# RFR24_AMS_Design_-_Power_Supply_V1.net
KiCad netlist of a schematic drawn in Altium Designer
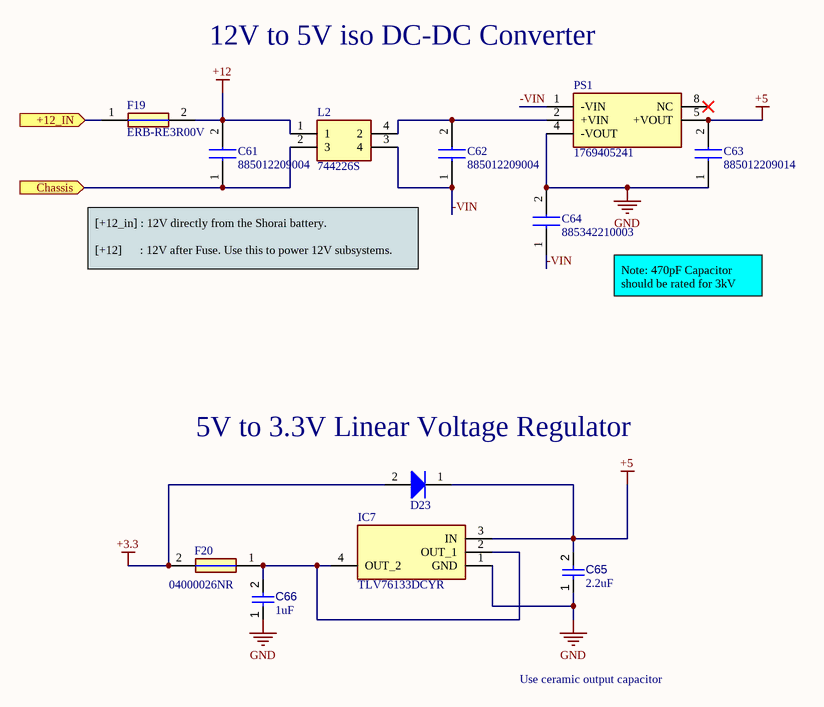
[diagram p0: RFR24 AMS Design - Power Supply V1.SchDoc]

(export (version "E")
  (design (tool "Eeschema 10.0.6"))
  (components
    (comp (ref "C61")
      (value "885012209004")
      (footprint "SamacSys:CAPC3225X220N")
      (description "Capacitor")
      (fields (field (name "MOUSER PART NUMBER") "710-885012209004"))
      (libsource (lib "*") (part "885012209004"))
    )
    (comp (ref "C62")
      (value "885012209004")
      (footprint "SamacSys:CAPC3225X220N")
      (description "Capacitor")
      (fields (field (name "MOUSER PART NUMBER") "710-885012209004"))
      (libsource (lib "*") (part "885012209004"))
    )
    (comp (ref "C63")
      (value "885012209014")
      (footprint "SamacSys:CAPC3225X220N")
      (description "Capacitor")
      (fields (field (name "MOUSER PART NUMBER") "710-885012209014"))
      (libsource (lib "*") (part "885012209014"))
    )
    (comp (ref "C64")
      (value "885342210003")
      (footprint "SamacSys:CAPC4620X220N")
      (description "Capacitor")
      (fields (field (name "MOUSER PART NUMBER") "710-885342210003"))
      (libsource (lib "*") (part "885342210003"))
    )
    (comp (ref "C65")
      (value "2.2uF")
      (footprint "CAPC2013X145X50LL20T25")
      (description "Chip Capacitor, 1 uF, +/-10%, 25 V, 0805 (2012 Metric)")
      (fields (field (name "TOLERANCE") "10%") (field (name "Comment") "Capacitor 1 uF +/- 10% 25 V 0805"))
      (libsource (lib "Rutgers University") (part "CAP-NP-2"))
    )
    (comp (ref "C66")
      (value "1uF")
      (footprint "CAPC2013X145X50LL20T25")
      (description "Chip Capacitor, 1 uF, +/-10%, 25 V, 0805 (2012 Metric)")
      (fields (field (name "TOLERANCE") "10%") (field (name "Comment") "Capacitor 1 uF +/- 10% 25 V 0805"))
      (libsource (lib "Rutgers University") (part "CAP-NP-2"))
    )
    (comp (ref "D23")
      (value "unknown")
      (footprint "INF-SOD323_V")
      (description "Silicon Schottky Diode, -55 to 125 degC, SOD323, Reel, Green")
      (fields (field (name "PARTNUMBER") "BAS170W") (field (name "MANUFACTURER") "Infineon"))
      (libsource (lib "Altium Content Vault") (part "INF-D_K1A2-2"))
    )
    (comp (ref "F19")
      (value "ERB-RE3R00V")
      (footprint "SamacSys:ERBRE0R50V")
      (description "Fuse")
      (fields (field (name "MOUSER PART NUMBER") "667-ERB-RE3R00V"))
      (libsource (lib "*") (part "ERB-RE3R00V"))
    )
    (comp (ref "F20")
      (value "04000026NR")
      (footprint "SamacSys:FUSC1508X58N")
      (description "Fuse")
      (fields (field (name "MOUSER PART NUMBER") "576-04000026NR"))
      (libsource (lib "*") (part "04000026NR"))
    )
    (comp (ref "IC7")
      (value "TLV76133DCYR")
      (footprint "SamacSys:SOT230P700X180-4N")
      (description "Integrated Circuit")
      (fields (field (name "MOUSER PART NUMBER") "595-TLV76133DCYR"))
      (libsource (lib "*") (part "TLV76133DCYR"))
    )
    (comp (ref "L2")
      (value "744226S")
      (footprint "SamacSys:WE-SL274")
      (description "Inductor")
      (fields (field (name "MOUSER PART NUMBER") "710-744226S"))
      (libsource (lib "*") (part "744226S"))
    )
    (comp (ref "PS1")
      (value "1769405241")
      (footprint "SamacSys:1769405241")
      (description "Power Supply")
      (libsource (lib "*") (part "1769405241"))
    )
  )
  (nets
    (net (code "1") (name "+3.3") (class "Default")
      (node (ref "D23") (pin "2") (pinfunction "A_2") (pintype "passive"))
      (node (ref "F20") (pin "2") (pinfunction "2_2") (pintype "passive"))
    )
    (net (code "2") (name "+5") (class "Default")
      (node (ref "C63") (pin "2") (pinfunction "2_2") (pintype "passive"))
      (node (ref "C65") (pin "2") (pinfunction "2_2") (pintype "passive"))
      (node (ref "D23") (pin "1") (pinfunction "K_1") (pintype "passive"))
      (node (ref "IC7") (pin "3") (pinfunction "IN_3") (pintype "passive"))
      (node (ref "PS1") (pin "5") (pinfunction "+VOUT_5") (pintype "passive"))
    )
    (net (code "3") (name "+12") (class "Default")
      (node (ref "C61") (pin "2") (pinfunction "2_2") (pintype "passive"))
      (node (ref "F19") (pin "2") (pinfunction "2_2") (pintype "passive"))
      (node (ref "L2") (pin "1") (pinfunction "1_1") (pintype "passive"))
    )
    (net (code "4") (name "/+12_IN") (class "Default")
      (node (ref "F19") (pin "1") (pinfunction "1_1") (pintype "passive"))
    )
    (net (code "5") (name "/-VIN") (class "Default")
      (node (ref "C62") (pin "1") (pinfunction "1_1") (pintype "passive"))
      (node (ref "C64") (pin "1") (pinfunction "1_1") (pintype "passive"))
      (node (ref "L2") (pin "3") (pinfunction "4_3") (pintype "passive"))
      (node (ref "PS1") (pin "1") (pinfunction "-VIN_1") (pintype "passive"))
    )
    (net (code "6") (name "/Chassis") (class "Default")
      (node (ref "C61") (pin "1") (pinfunction "1_1") (pintype "passive"))
      (node (ref "L2") (pin "2") (pinfunction "3_2") (pintype "passive"))
    )
    (net (code "7") (name "GND") (class "Default")
      (node (ref "C63") (pin "1") (pinfunction "1_1") (pintype "passive"))
      (node (ref "C64") (pin "2") (pinfunction "2_2") (pintype "passive"))
      (node (ref "C65") (pin "1") (pinfunction "1_1") (pintype "passive"))
      (node (ref "C66") (pin "1") (pinfunction "1_1") (pintype "passive"))
      (node (ref "IC7") (pin "1") (pinfunction "GND_1") (pintype "passive"))
      (node (ref "PS1") (pin "4") (pinfunction "-VOUT_4") (pintype "passive"))
    )
    (net (code "8") (name "Net-(IC7-OUT_1)") (class "Default")
      (node (ref "C66") (pin "2") (pinfunction "2_2") (pintype "passive"))
      (node (ref "F20") (pin "1") (pinfunction "1_1") (pintype "passive"))
      (node (ref "IC7") (pin "2") (pinfunction "OUT_1_2") (pintype "passive"))
      (node (ref "IC7") (pin "4") (pinfunction "OUT_2_4") (pintype "passive"))
    )
    (net (code "9") (name "Net-(L2-2)") (class "Default")
      (node (ref "C62") (pin "2") (pinfunction "2_2") (pintype "passive"))
      (node (ref "L2") (pin "4") (pinfunction "2_4") (pintype "passive"))
      (node (ref "PS1") (pin "2") (pinfunction "+VIN_2") (pintype "passive"))
    )
    (net (code "10") (name "unconnected-(PS1-NC-Pad8)") (class "Default")
      (node (ref "PS1") (pin "8") (pinfunction "NC_8") (pintype "passive+no_connect"))
    )
  )
)
